# Chroma-Color.net
KiCad netlist of a schematic drawn in EAGLE
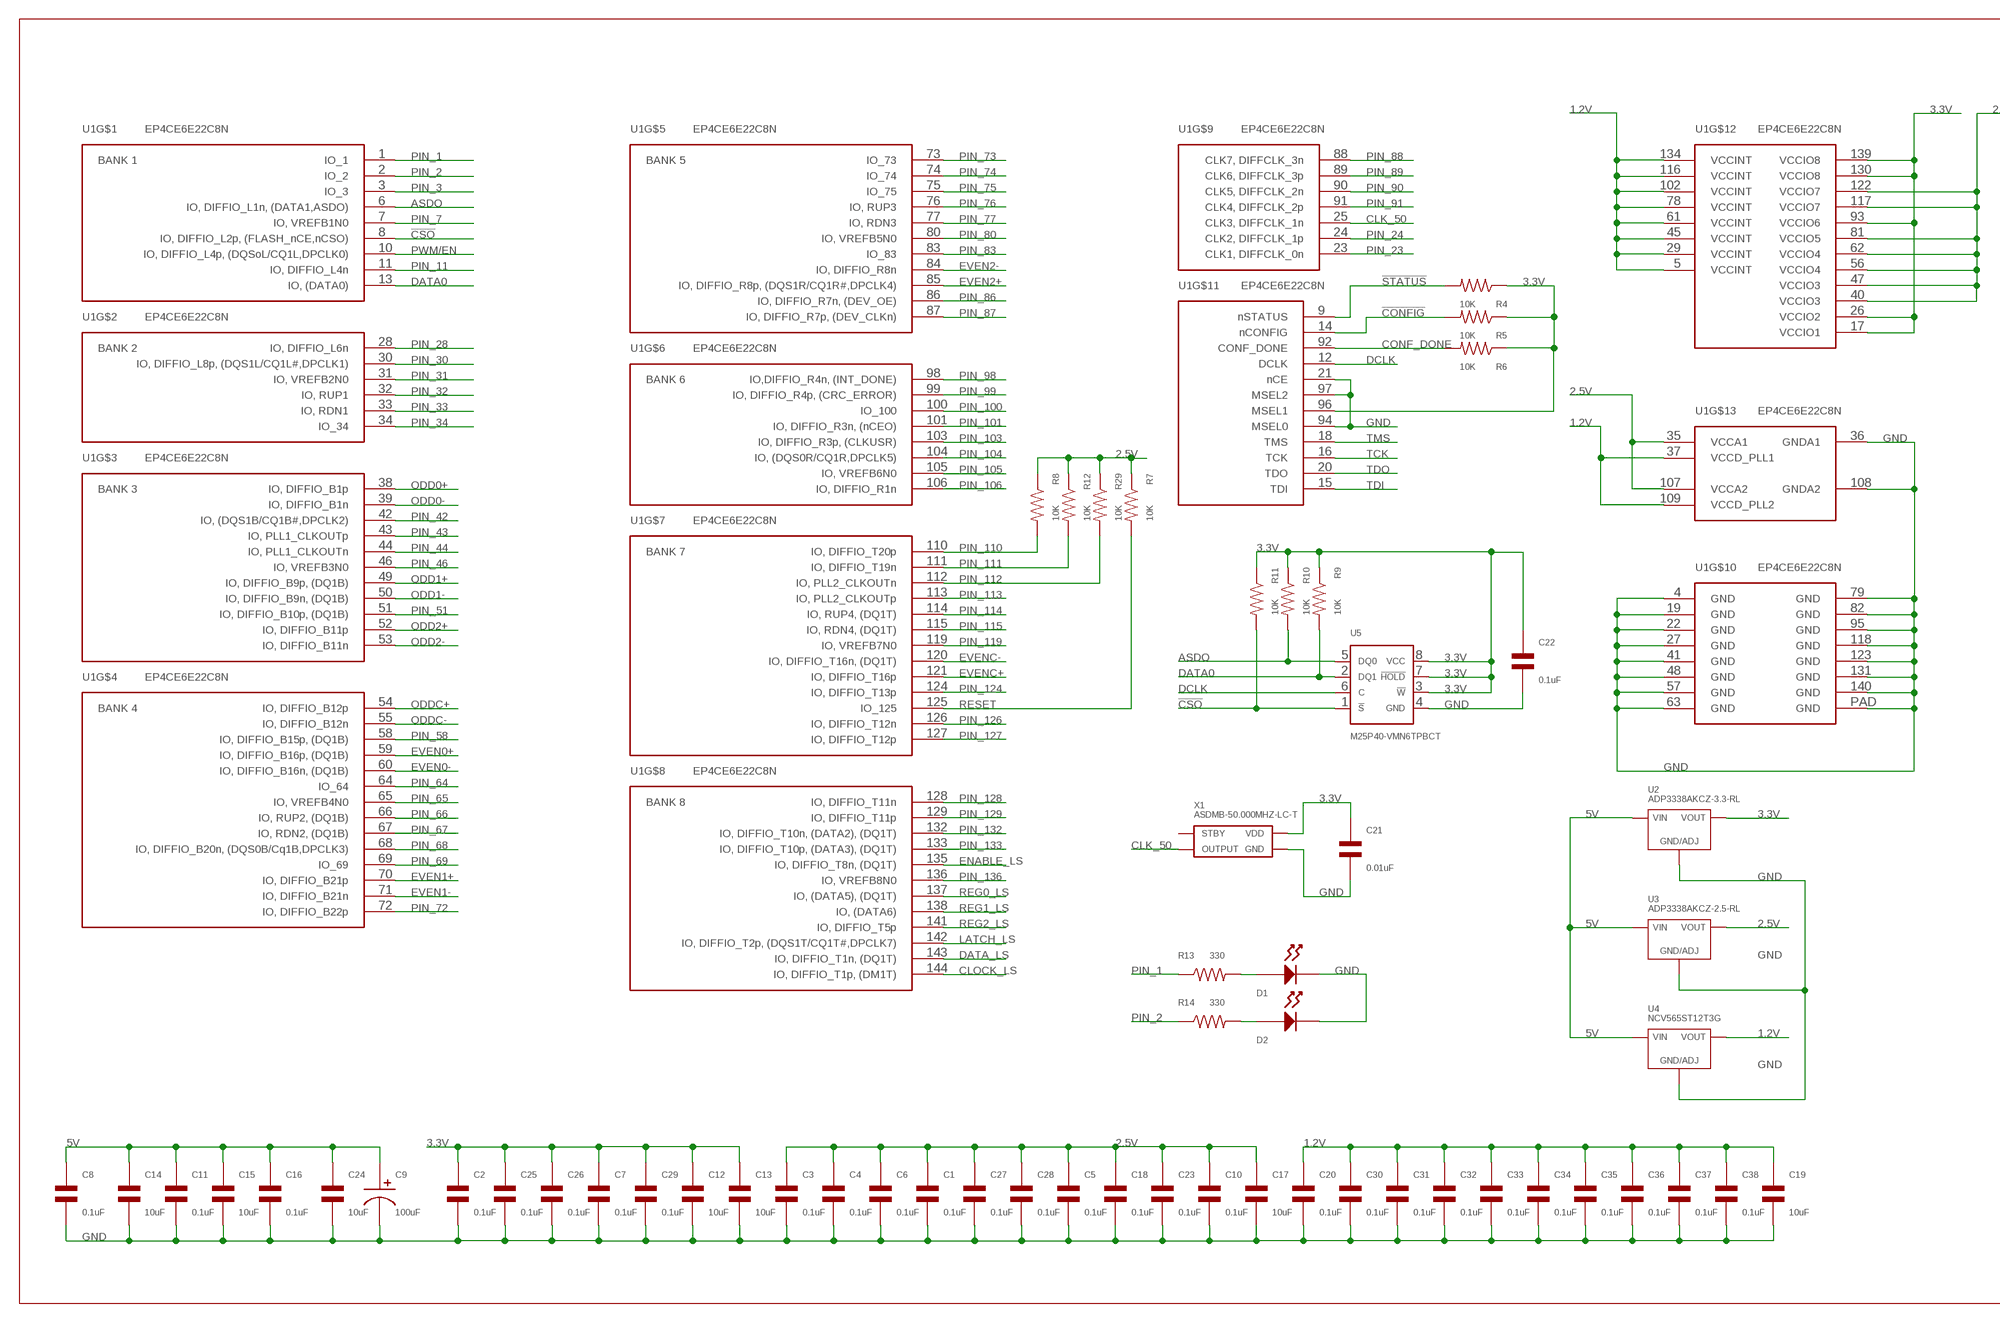
[diagram p0: schematic, sheet 1, part 1 of 2]
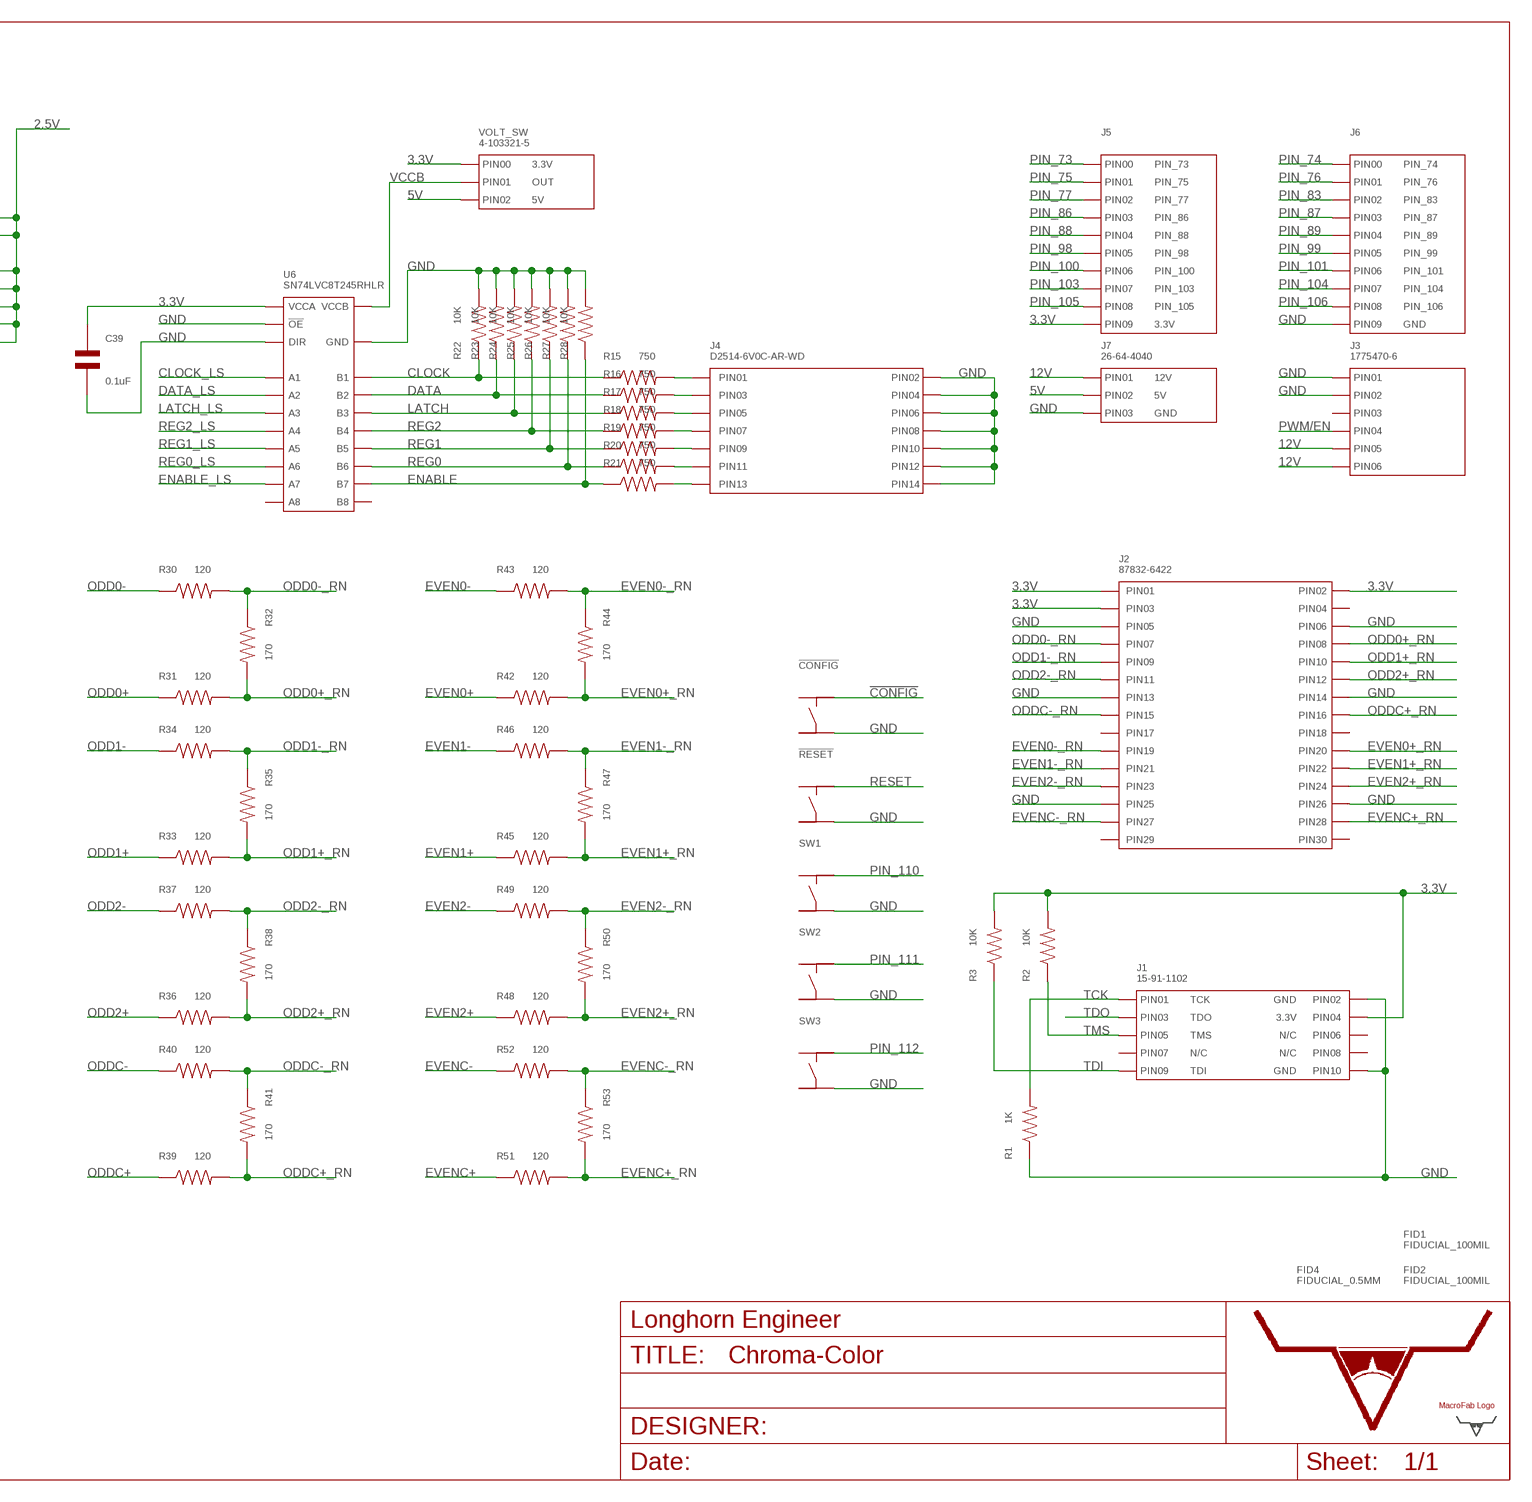
[diagram p1: schematic, sheet 1, part 2 of 2]

(export (version "E")
  (design (tool "Eeschema 10.0.6"))
  (components
    (comp (ref "!CONFIG")
      (value "TACT_4.2MM")
      (footprint "eagle-import:TACT4.2MM")
      (libsource (lib "eagle-import") (part "TACT_4.2MM"))
    )
    (comp (ref "!RESET")
      (value "TACT_4.2MM")
      (footprint "eagle-import:TACT4.2MM")
      (libsource (lib "eagle-import") (part "TACT_4.2MM"))
    )
    (comp (ref "C1")
      (value "0.1uF")
      (footprint "eagle-import:C0603")
      (libsource (lib "eagle-import") (part "CAPACITOR_NP_0603"))
    )
    (comp (ref "C2")
      (value "0.1uF")
      (footprint "eagle-import:C0603")
      (libsource (lib "eagle-import") (part "CAPACITOR_NP_0603"))
    )
    (comp (ref "C3")
      (value "0.1uF")
      (footprint "eagle-import:C0603")
      (libsource (lib "eagle-import") (part "CAPACITOR_NP_0603"))
    )
    (comp (ref "C4")
      (value "0.1uF")
      (footprint "eagle-import:C0603")
      (libsource (lib "eagle-import") (part "CAPACITOR_NP_0603"))
    )
    (comp (ref "C5")
      (value "0.1uF")
      (footprint "eagle-import:C0603")
      (libsource (lib "eagle-import") (part "CAPACITOR_NP_0603"))
    )
    (comp (ref "C6")
      (value "0.1uF")
      (footprint "eagle-import:C0603")
      (libsource (lib "eagle-import") (part "CAPACITOR_NP_0603"))
    )
    (comp (ref "C7")
      (value "0.1uF")
      (footprint "eagle-import:C0603")
      (libsource (lib "eagle-import") (part "CAPACITOR_NP_0603"))
    )
    (comp (ref "C8")
      (value "0.1uF")
      (footprint "eagle-import:C0603")
      (libsource (lib "eagle-import") (part "CAPACITOR_NP_0603"))
    )
    (comp (ref "C9")
      (value "100uF")
      (footprint "eagle-import:CP6.3MM")
      (libsource (lib "eagle-import") (part "CAPACITOR_P_6.3MM"))
    )
    (comp (ref "C10")
      (value "0.1uF")
      (footprint "eagle-import:C0603")
      (libsource (lib "eagle-import") (part "CAPACITOR_NP_0603"))
    )
    (comp (ref "C11")
      (value "0.1uF")
      (footprint "eagle-import:C0603")
      (libsource (lib "eagle-import") (part "CAPACITOR_NP_0603"))
    )
    (comp (ref "C12")
      (value "10uF")
      (footprint "eagle-import:C0603")
      (libsource (lib "eagle-import") (part "CAPACITOR_NP_0603"))
    )
    (comp (ref "C13")
      (value "10uF")
      (footprint "eagle-import:C0603")
      (libsource (lib "eagle-import") (part "CAPACITOR_NP_0603"))
    )
    (comp (ref "C14")
      (value "10uF")
      (footprint "eagle-import:C0603")
      (libsource (lib "eagle-import") (part "CAPACITOR_NP_0603"))
    )
    (comp (ref "C15")
      (value "10uF")
      (footprint "eagle-import:C0603")
      (libsource (lib "eagle-import") (part "CAPACITOR_NP_0603"))
    )
    (comp (ref "C16")
      (value "0.1uF")
      (footprint "eagle-import:C0603")
      (libsource (lib "eagle-import") (part "CAPACITOR_NP_0603"))
    )
    (comp (ref "C17")
      (value "10uF")
      (footprint "eagle-import:C0603")
      (libsource (lib "eagle-import") (part "CAPACITOR_NP_0603"))
    )
    (comp (ref "C18")
      (value "0.1uF")
      (footprint "eagle-import:C0603")
      (libsource (lib "eagle-import") (part "CAPACITOR_NP_0603"))
    )
    (comp (ref "C19")
      (value "10uF")
      (footprint "eagle-import:C0603")
      (libsource (lib "eagle-import") (part "CAPACITOR_NP_0603"))
    )
    (comp (ref "C20")
      (value "0.1uF")
      (footprint "eagle-import:C0603")
      (libsource (lib "eagle-import") (part "CAPACITOR_NP_0603"))
    )
    (comp (ref "C21")
      (value "0.01uF")
      (footprint "eagle-import:C0603")
      (libsource (lib "eagle-import") (part "CAPACITOR_NP_0603"))
    )
    (comp (ref "C22")
      (value "0.1uF")
      (footprint "eagle-import:C0603")
      (libsource (lib "eagle-import") (part "CAPACITOR_NP_0603"))
    )
    (comp (ref "C23")
      (value "0.1uF")
      (footprint "eagle-import:C0603")
      (libsource (lib "eagle-import") (part "CAPACITOR_NP_0603"))
    )
    (comp (ref "C24")
      (value "10uF")
      (footprint "eagle-import:C0603")
      (libsource (lib "eagle-import") (part "CAPACITOR_NP_0603"))
    )
    (comp (ref "C25")
      (value "0.1uF")
      (footprint "eagle-import:C0603")
      (libsource (lib "eagle-import") (part "CAPACITOR_NP_0603"))
    )
    (comp (ref "C26")
      (value "0.1uF")
      (footprint "eagle-import:C0603")
      (libsource (lib "eagle-import") (part "CAPACITOR_NP_0603"))
    )
    (comp (ref "C27")
      (value "0.1uF")
      (footprint "eagle-import:C0603")
      (libsource (lib "eagle-import") (part "CAPACITOR_NP_0603"))
    )
    (comp (ref "C28")
      (value "0.1uF")
      (footprint "eagle-import:C0603")
      (libsource (lib "eagle-import") (part "CAPACITOR_NP_0603"))
    )
    (comp (ref "C29")
      (value "0.1uF")
      (footprint "eagle-import:C0603")
      (libsource (lib "eagle-import") (part "CAPACITOR_NP_0603"))
    )
    (comp (ref "C30")
      (value "0.1uF")
      (footprint "eagle-import:C0603")
      (libsource (lib "eagle-import") (part "CAPACITOR_NP_0603"))
    )
    (comp (ref "C31")
      (value "0.1uF")
      (footprint "eagle-import:C0603")
      (libsource (lib "eagle-import") (part "CAPACITOR_NP_0603"))
    )
    (comp (ref "C32")
      (value "0.1uF")
      (footprint "eagle-import:C0603")
      (libsource (lib "eagle-import") (part "CAPACITOR_NP_0603"))
    )
    (comp (ref "C33")
      (value "0.1uF")
      (footprint "eagle-import:C0603")
      (libsource (lib "eagle-import") (part "CAPACITOR_NP_0603"))
    )
    (comp (ref "C34")
      (value "0.1uF")
      (footprint "eagle-import:C0603")
      (libsource (lib "eagle-import") (part "CAPACITOR_NP_0603"))
    )
    (comp (ref "C35")
      (value "0.1uF")
      (footprint "eagle-import:C0603")
      (libsource (lib "eagle-import") (part "CAPACITOR_NP_0603"))
    )
    (comp (ref "C36")
      (value "0.1uF")
      (footprint "eagle-import:C0603")
      (libsource (lib "eagle-import") (part "CAPACITOR_NP_0603"))
    )
    (comp (ref "C37")
      (value "0.1uF")
      (footprint "eagle-import:C0603")
      (libsource (lib "eagle-import") (part "CAPACITOR_NP_0603"))
    )
    (comp (ref "C38")
      (value "0.1uF")
      (footprint "eagle-import:C0603")
      (libsource (lib "eagle-import") (part "CAPACITOR_NP_0603"))
    )
    (comp (ref "C39")
      (value "0.1uF")
      (footprint "eagle-import:C0603")
      (libsource (lib "eagle-import") (part "CAPACITOR_NP_0603"))
    )
    (comp (ref "D1")
      (value "LED_SINGLE_0805")
      (footprint "eagle-import:LED0805")
      (libsource (lib "eagle-import") (part "LED_SINGLE_0805"))
    )
    (comp (ref "D2")
      (value "LED_SINGLE_0805")
      (footprint "eagle-import:LED0805")
      (libsource (lib "eagle-import") (part "LED_SINGLE_0805"))
    )
    (comp (ref "FID1")
      (value "FIDUCIAL_100MIL")
      (footprint "eagle-import:FIDUCIAL_100MIL")
      (libsource (lib "eagle-import") (part "FIDUCIAL_100MIL"))
    )
    (comp (ref "FID2")
      (value "FIDUCIAL_100MIL")
      (footprint "eagle-import:FIDUCIAL_100MIL")
      (libsource (lib "eagle-import") (part "FIDUCIAL_100MIL"))
    )
    (comp (ref "FID4")
      (value "FIDUCIAL_0.5MM")
      (footprint "eagle-import:FIDUCIAL_0.5MM")
      (libsource (lib "eagle-import") (part "FIDUCIAL_0.5MM"))
    )
    (comp (ref "J1")
      (value "15-91-1102")
      (footprint "eagle-import:15-91-1102")
      (fields
        (field (name "LABEL01") "TCK")
        (field (name "LABEL02") "GND")
        (field (name "LABEL03") "TDO")
        (field (name "LABEL04") "3.3V")
        (field (name "LABEL05") "TMS")
        (field (name "LABEL06") "N/C")
        (field (name "LABEL07") "N/C")
        (field (name "LABEL08") "N/C")
        (field (name "LABEL09") "TDI")
        (field (name "LABEL10") "GND")
      )
      (libsource (lib "eagle-import") (part "CON_02X05_15-91-1102"))
    )
    (comp (ref "J2")
      (value "87832-6422")
      (footprint "eagle-import:87832-6422")
      (libsource (lib "eagle-import") (part "CON_02X15_87832-6422"))
    )
    (comp (ref "J3")
      (value "1775470-6")
      (footprint "eagle-import:1775470-6")
      (libsource (lib "eagle-import") (part "CON_01X06_1775470-6"))
    )
    (comp (ref "J4")
      (value "D2514-6V0C-AR-WD")
      (footprint "eagle-import:D2514-6V0C-AR-WD")
      (libsource (lib "eagle-import") (part "CON_02X07_D2514-6V0C-AR-WD"))
    )
    (comp (ref "J5")
      (value "HEADER_01X10_PTH_2.54MM")
      (footprint "eagle-import:PTH_2.54MM_01X10")
      (fields
        (field (name "LABEL00") "PIN_73")
        (field (name "LABEL01") "PIN_75")
        (field (name "LABEL02") "PIN_77")
        (field (name "LABEL03") "PIN_86")
        (field (name "LABEL04") "PIN_88")
        (field (name "LABEL05") "PIN_98")
        (field (name "LABEL06") "PIN_100")
        (field (name "LABEL07") "PIN_103")
        (field (name "LABEL08") "PIN_105")
        (field (name "LABEL09") "3.3V")
      )
      (libsource (lib "eagle-import") (part "HEADER_01X10_PTH_2.54MM"))
    )
    (comp (ref "J6")
      (value "HEADER_01X10_PTH_2.54MM")
      (footprint "eagle-import:PTH_2.54MM_01X10")
      (fields
        (field (name "LABEL00") "PIN_74")
        (field (name "LABEL01") "PIN_76")
        (field (name "LABEL02") "PIN_83")
        (field (name "LABEL03") "PIN_87")
        (field (name "LABEL04") "PIN_89")
        (field (name "LABEL05") "PIN_99")
        (field (name "LABEL06") "PIN_101")
        (field (name "LABEL07") "PIN_104")
        (field (name "LABEL08") "PIN_106")
        (field (name "LABEL09") "GND")
      )
      (libsource (lib "eagle-import") (part "HEADER_01X10_PTH_2.54MM"))
    )
    (comp (ref "J7")
      (value "26-64-4040")
      (footprint "eagle-import:26-64-4040(KEYPIN1)")
      (fields (field (name "LABEL01") "12V") (field (name "LABEL02") "5V") (field (name "LABEL03") "GND"))
      (libsource (lib "eagle-import") (part "CON_01X03_26-64-4040_(KEYPIN1)"))
    )
    (comp (ref "R1")
      (value "1K")
      (footprint "eagle-import:R0603")
      (libsource (lib "eagle-import") (part "RESISTOR_0603"))
    )
    (comp (ref "R2")
      (value "10K")
      (footprint "eagle-import:R0603")
      (libsource (lib "eagle-import") (part "RESISTOR_0603"))
    )
    (comp (ref "R3")
      (value "10K")
      (footprint "eagle-import:R0603")
      (libsource (lib "eagle-import") (part "RESISTOR_0603"))
    )
    (comp (ref "R4")
      (value "10K")
      (footprint "eagle-import:R0603")
      (libsource (lib "eagle-import") (part "RESISTOR_0603"))
    )
    (comp (ref "R5")
      (value "10K")
      (footprint "eagle-import:R0603")
      (libsource (lib "eagle-import") (part "RESISTOR_0603"))
    )
    (comp (ref "R6")
      (value "10K")
      (footprint "eagle-import:R0603")
      (libsource (lib "eagle-import") (part "RESISTOR_0603"))
    )
    (comp (ref "R7")
      (value "10K")
      (footprint "eagle-import:R0603")
      (libsource (lib "eagle-import") (part "RESISTOR_0603"))
    )
    (comp (ref "R8")
      (value "10K")
      (footprint "eagle-import:R0603")
      (libsource (lib "eagle-import") (part "RESISTOR_0603"))
    )
    (comp (ref "R9")
      (value "10K")
      (footprint "eagle-import:R0603")
      (libsource (lib "eagle-import") (part "RESISTOR_0603"))
    )
    (comp (ref "R10")
      (value "10K")
      (footprint "eagle-import:R0603")
      (libsource (lib "eagle-import") (part "RESISTOR_0603"))
    )
    (comp (ref "R11")
      (value "10K")
      (footprint "eagle-import:R0603")
      (libsource (lib "eagle-import") (part "RESISTOR_0603"))
    )
    (comp (ref "R12")
      (value "10K")
      (footprint "eagle-import:R0603")
      (libsource (lib "eagle-import") (part "RESISTOR_0603"))
    )
    (comp (ref "R13")
      (value "330")
      (footprint "eagle-import:R0603")
      (libsource (lib "eagle-import") (part "RESISTOR_0603"))
    )
    (comp (ref "R14")
      (value "330")
      (footprint "eagle-import:R0603")
      (libsource (lib "eagle-import") (part "RESISTOR_0603"))
    )
    (comp (ref "R15")
      (value "750")
      (footprint "eagle-import:R0603")
      (libsource (lib "eagle-import") (part "RESISTOR_0603"))
    )
    (comp (ref "R16")
      (value "750")
      (footprint "eagle-import:R0603")
      (libsource (lib "eagle-import") (part "RESISTOR_0603"))
    )
    (comp (ref "R17")
      (value "750")
      (footprint "eagle-import:R0603")
      (libsource (lib "eagle-import") (part "RESISTOR_0603"))
    )
    (comp (ref "R18")
      (value "750")
      (footprint "eagle-import:R0603")
      (libsource (lib "eagle-import") (part "RESISTOR_0603"))
    )
    (comp (ref "R19")
      (value "750")
      (footprint "eagle-import:R0603")
      (libsource (lib "eagle-import") (part "RESISTOR_0603"))
    )
    (comp (ref "R20")
      (value "750")
      (footprint "eagle-import:R0603")
      (libsource (lib "eagle-import") (part "RESISTOR_0603"))
    )
    (comp (ref "R21")
      (value "750")
      (footprint "eagle-import:R0603")
      (libsource (lib "eagle-import") (part "RESISTOR_0603"))
    )
    (comp (ref "R22")
      (value "10K")
      (footprint "eagle-import:R0603")
      (libsource (lib "eagle-import") (part "RESISTOR_0603"))
    )
    (comp (ref "R23")
      (value "10K")
      (footprint "eagle-import:R0603")
      (libsource (lib "eagle-import") (part "RESISTOR_0603"))
    )
    (comp (ref "R24")
      (value "10K")
      (footprint "eagle-import:R0603")
      (libsource (lib "eagle-import") (part "RESISTOR_0603"))
    )
    (comp (ref "R25")
      (value "10K")
      (footprint "eagle-import:R0603")
      (libsource (lib "eagle-import") (part "RESISTOR_0603"))
    )
    (comp (ref "R26")
      (value "10K")
      (footprint "eagle-import:R0603")
      (libsource (lib "eagle-import") (part "RESISTOR_0603"))
    )
    (comp (ref "R27")
      (value "10K")
      (footprint "eagle-import:R0603")
      (libsource (lib "eagle-import") (part "RESISTOR_0603"))
    )
    (comp (ref "R28")
      (value "10K")
      (footprint "eagle-import:R0603")
      (libsource (lib "eagle-import") (part "RESISTOR_0603"))
    )
    (comp (ref "R29")
      (value "10K")
      (footprint "eagle-import:R0603")
      (libsource (lib "eagle-import") (part "RESISTOR_0603"))
    )
    (comp (ref "R30")
      (value "120")
      (footprint "eagle-import:R0402")
      (libsource (lib "eagle-import") (part "RESISTOR_0402"))
    )
    (comp (ref "R31")
      (value "120")
      (footprint "eagle-import:R0402")
      (libsource (lib "eagle-import") (part "RESISTOR_0402"))
    )
    (comp (ref "R32")
      (value "170")
      (footprint "eagle-import:R0402")
      (libsource (lib "eagle-import") (part "RESISTOR_0402"))
    )
    (comp (ref "R33")
      (value "120")
      (footprint "eagle-import:R0402")
      (libsource (lib "eagle-import") (part "RESISTOR_0402"))
    )
    (comp (ref "R34")
      (value "120")
      (footprint "eagle-import:R0402")
      (libsource (lib "eagle-import") (part "RESISTOR_0402"))
    )
    (comp (ref "R35")
      (value "170")
      (footprint "eagle-import:R0402")
      (libsource (lib "eagle-import") (part "RESISTOR_0402"))
    )
    (comp (ref "R36")
      (value "120")
      (footprint "eagle-import:R0402")
      (libsource (lib "eagle-import") (part "RESISTOR_0402"))
    )
    (comp (ref "R37")
      (value "120")
      (footprint "eagle-import:R0402")
      (libsource (lib "eagle-import") (part "RESISTOR_0402"))
    )
    (comp (ref "R38")
      (value "170")
      (footprint "eagle-import:R0402")
      (libsource (lib "eagle-import") (part "RESISTOR_0402"))
    )
    (comp (ref "R39")
      (value "120")
      (footprint "eagle-import:R0402")
      (libsource (lib "eagle-import") (part "RESISTOR_0402"))
    )
    (comp (ref "R40")
      (value "120")
      (footprint "eagle-import:R0402")
      (libsource (lib "eagle-import") (part "RESISTOR_0402"))
    )
    (comp (ref "R41")
      (value "170")
      (footprint "eagle-import:R0402")
      (libsource (lib "eagle-import") (part "RESISTOR_0402"))
    )
    (comp (ref "R42")
      (value "120")
      (footprint "eagle-import:R0402")
      (libsource (lib "eagle-import") (part "RESISTOR_0402"))
    )
    (comp (ref "R43")
      (value "120")
      (footprint "eagle-import:R0402")
      (libsource (lib "eagle-import") (part "RESISTOR_0402"))
    )
    (comp (ref "R44")
      (value "170")
      (footprint "eagle-import:R0402")
      (libsource (lib "eagle-import") (part "RESISTOR_0402"))
    )
    (comp (ref "R45")
      (value "120")
      (footprint "eagle-import:R0402")
      (libsource (lib "eagle-import") (part "RESISTOR_0402"))
    )
    (comp (ref "R46")
      (value "120")
      (footprint "eagle-import:R0402")
      (libsource (lib "eagle-import") (part "RESISTOR_0402"))
    )
    (comp (ref "R47")
      (value "170")
      (footprint "eagle-import:R0402")
      (libsource (lib "eagle-import") (part "RESISTOR_0402"))
    )
    (comp (ref "R48")
      (value "120")
      (footprint "eagle-import:R0402")
      (libsource (lib "eagle-import") (part "RESISTOR_0402"))
    )
    (comp (ref "R49")
      (value "120")
      (footprint "eagle-import:R0402")
      (libsource (lib "eagle-import") (part "RESISTOR_0402"))
    )
    (comp (ref "R50")
      (value "170")
      (footprint "eagle-import:R0402")
      (libsource (lib "eagle-import") (part "RESISTOR_0402"))
    )
    (comp (ref "R51")
      (value "120")
      (footprint "eagle-import:R0402")
      (libsource (lib "eagle-import") (part "RESISTOR_0402"))
    )
    (comp (ref "R52")
      (value "120")
      (footprint "eagle-import:R0402")
      (libsource (lib "eagle-import") (part "RESISTOR_0402"))
    )
    (comp (ref "R53")
      (value "170")
      (footprint "eagle-import:R0402")
      (libsource (lib "eagle-import") (part "RESISTOR_0402"))
    )
    (comp (ref "SW1")
      (value "TACT_4.2MM")
      (footprint "eagle-import:TACT4.2MM")
      (libsource (lib "eagle-import") (part "TACT_4.2MM"))
    )
    (comp (ref "SW2")
      (value "TACT_4.2MM")
      (footprint "eagle-import:TACT4.2MM")
      (libsource (lib "eagle-import") (part "TACT_4.2MM"))
    )
    (comp (ref "SW3")
      (value "TACT_4.2MM")
      (footprint "eagle-import:TACT4.2MM")
      (libsource (lib "eagle-import") (part "TACT_4.2MM"))
    )
    (comp (ref "U$1")
      (value "LHE_FRAME")
      (footprint "eagle-import:LHE_FRAME")
      (fields (field (name "DNAME") "Parker Dillmann") (field (name "REVNUM") "REV: 2"))
      (libsource (lib "eagle-import") (part "LHE_FRAME"))
    )
    (comp (ref "U$2")
      (value "MF_LOGOLOGO_MEDIUM")
      (footprint "eagle-import:MF_LOGO_MEDIUM")
      (libsource (lib "eagle-import") (part "MF_LOGOLOGO_MEDIUM"))
    )
    (comp (ref "U$3")
      (value "LHE_LOGOLHE_LOGO")
      (footprint "eagle-import:LHE_LOGO")
      (libsource (lib "eagle-import") (part "LHE_LOGOLHE_LOGO"))
    )
    (comp (ref "U1")
      (value "EP4CE6E22C8N")
      (footprint "eagle-import:EQFP-144")
      (libsource (lib "eagle-import") (part "EP4CE6E22C8N"))
    )
    (comp (ref "U2")
      (value "ADP3338AKCZ-3.3-RL")
      (footprint "eagle-import:ADP3338_SOT-223-3")
      (libsource (lib "eagle-import") (part "LINEAR_VOTLAGE_REGULATORS_ADP3338"))
    )
    (comp (ref "U3")
      (value "ADP3338AKCZ-2.5-RL")
      (footprint "eagle-import:ADP3338_SOT-223-3")
      (libsource (lib "eagle-import") (part "LINEAR_VOTLAGE_REGULATORS_ADP3338"))
    )
    (comp (ref "U4")
      (value "NCV565ST12T3G")
      (footprint "eagle-import:NCV565_SOT-223-3")
      (libsource (lib "eagle-import") (part "LINEAR_VOTLAGE_REGULATORS_NCV565ST12T3G"))
    )
    (comp (ref "U5")
      (value "M25P40-VMN6TPBCT")
      (footprint "eagle-import:M25P40_SOIC-8")
      (libsource (lib "eagle-import") (part "M25P40-VMN6TPBCT"))
    )
    (comp (ref "U6")
      (value "SN74LVC8T245RHLR")
      (footprint "eagle-import:SN74LVC8T245_VQFN-24")
      (libsource (lib "eagle-import") (part "SN74LVC8T245_RHL"))
    )
    (comp (ref "VOLT_SW")
      (value "4-103321-5")
      (footprint "eagle-import:PTH_2.54MM_01X03")
      (fields (field (name "LABEL00") "3.3V") (field (name "LABEL01") "OUT") (field (name "LABEL02") "5V"))
      (libsource (lib "eagle-import") (part "HEADER_01X03_PTH_2.54MM"))
    )
    (comp (ref "X1")
      (value "ASDMB-50.000MHZ-LC-T")
      (footprint "eagle-import:ASDMB")
      (libsource (lib "eagle-import") (part "ASDMB"))
    )
  )
  (nets
    (net (code "1") (name "/1.2V") (class "Default")
      (node (ref "C19") (pin "P$1") (pinfunction "P$1_P$1") (pintype "passive"))
      (node (ref "C20") (pin "P$1") (pinfunction "P$1_P$1") (pintype "passive"))
      (node (ref "C30") (pin "P$1") (pinfunction "P$1_P$1") (pintype "passive"))
      (node (ref "C31") (pin "P$1") (pinfunction "P$1_P$1") (pintype "passive"))
      (node (ref "C32") (pin "P$1") (pinfunction "P$1_P$1") (pintype "passive"))
      (node (ref "C33") (pin "P$1") (pinfunction "P$1_P$1") (pintype "passive"))
      (node (ref "C34") (pin "P$1") (pinfunction "P$1_P$1") (pintype "passive"))
      (node (ref "C35") (pin "P$1") (pinfunction "P$1_P$1") (pintype "passive"))
      (node (ref "C36") (pin "P$1") (pinfunction "P$1_P$1") (pintype "passive"))
      (node (ref "C37") (pin "P$1") (pinfunction "P$1_P$1") (pintype "passive"))
      (node (ref "C38") (pin "P$1") (pinfunction "P$1_P$1") (pintype "passive"))
      (node (ref "U1") (pin "102") (pinfunction "102_102") (pintype "bidirectional"))
      (node (ref "U1") (pin "109") (pinfunction "109_109") (pintype "bidirectional"))
      (node (ref "U1") (pin "116") (pinfunction "116_116") (pintype "bidirectional"))
      (node (ref "U1") (pin "134") (pinfunction "134_134") (pintype "bidirectional"))
      (node (ref "U1") (pin "29") (pinfunction "29_29") (pintype "bidirectional"))
      (node (ref "U1") (pin "37") (pinfunction "37_37") (pintype "bidirectional"))
      (node (ref "U1") (pin "45") (pinfunction "45_45") (pintype "bidirectional"))
      (node (ref "U1") (pin "5") (pinfunction "5_5") (pintype "bidirectional"))
      (node (ref "U1") (pin "61") (pinfunction "61_61") (pintype "bidirectional"))
      (node (ref "U1") (pin "78") (pinfunction "78_78") (pintype "bidirectional"))
      (node (ref "U4") (pin "2") (pinfunction "OUT_2") (pintype "bidirectional"))
      (node (ref "U4") (pin "PAD") (pinfunction "OUT_PAD") (pintype "bidirectional"))
    )
    (net (code "2") (name "/2.5V") (class "Default")
      (node (ref "C1") (pin "P$1") (pinfunction "P$1_P$1") (pintype "passive"))
      (node (ref "C10") (pin "P$1") (pinfunction "P$1_P$1") (pintype "passive"))
      (node (ref "C17") (pin "P$1") (pinfunction "P$1_P$1") (pintype "passive"))
      (node (ref "C18") (pin "P$1") (pinfunction "P$1_P$1") (pintype "passive"))
      (node (ref "C23") (pin "P$1") (pinfunction "P$1_P$1") (pintype "passive"))
      (node (ref "C27") (pin "P$1") (pinfunction "P$1_P$1") (pintype "passive"))
      (node (ref "C28") (pin "P$1") (pinfunction "P$1_P$1") (pintype "passive"))
      (node (ref "C3") (pin "P$1") (pinfunction "P$1_P$1") (pintype "passive"))
      (node (ref "C4") (pin "P$1") (pinfunction "P$1_P$1") (pintype "passive"))
      (node (ref "C5") (pin "P$1") (pinfunction "P$1_P$1") (pintype "passive"))
      (node (ref "C6") (pin "P$1") (pinfunction "P$1_P$1") (pintype "passive"))
      (node (ref "R12") (pin "P$1") (pinfunction "P$1_P$1") (pintype "passive"))
      (node (ref "R29") (pin "P$1") (pinfunction "P$1_P$1") (pintype "passive"))
      (node (ref "R7") (pin "P$1") (pinfunction "P$1_P$1") (pintype "passive"))
      (node (ref "R8") (pin "P$1") (pinfunction "P$1_P$1") (pintype "passive"))
      (node (ref "U1") (pin "107") (pinfunction "107_107") (pintype "bidirectional"))
      (node (ref "U1") (pin "117") (pinfunction "117_117") (pintype "bidirectional"))
      (node (ref "U1") (pin "122") (pinfunction "122_122") (pintype "bidirectional"))
      (node (ref "U1") (pin "35") (pinfunction "35_35") (pintype "bidirectional"))
      (node (ref "U1") (pin "40") (pinfunction "40_40") (pintype "bidirectional"))
      (node (ref "U1") (pin "47") (pinfunction "47_47") (pintype "bidirectional"))
      (node (ref "U1") (pin "56") (pinfunction "56_56") (pintype "bidirectional"))
      (node (ref "U1") (pin "62") (pinfunction "62_62") (pintype "bidirectional"))
      (node (ref "U1") (pin "81") (pinfunction "81_81") (pintype "bidirectional"))
      (node (ref "U3") (pin "2") (pinfunction "OUT_2") (pintype "bidirectional"))
      (node (ref "U3") (pin "PAD") (pinfunction "OUT_PAD") (pintype "bidirectional"))
    )
    (net (code "3") (name "/3.3V") (class "Default")
      (node (ref "C12") (pin "P$1") (pinfunction "P$1_P$1") (pintype "passive"))
      (node (ref "C13") (pin "P$1") (pinfunction "P$1_P$1") (pintype "passive"))
      (node (ref "C2") (pin "P$1") (pinfunction "P$1_P$1") (pintype "passive"))
      (node (ref "C21") (pin "P$1") (pinfunction "P$1_P$1") (pintype "passive"))
      (node (ref "C22") (pin "P$1") (pinfunction "P$1_P$1") (pintype "passive"))
      (node (ref "C25") (pin "P$1") (pinfunction "P$1_P$1") (pintype "passive"))
      (node (ref "C26") (pin "P$1") (pinfunction "P$1_P$1") (pintype "passive"))
      (node (ref "C29") (pin "P$1") (pinfunction "P$1_P$1") (pintype "passive"))
      (node (ref "C39") (pin "P$1") (pinfunction "P$1_P$1") (pintype "passive"))
      (node (ref "C7") (pin "P$1") (pinfunction "P$1_P$1") (pintype "passive"))
      (node (ref "J1") (pin "4") (pinfunction "PIN4_4") (pintype "bidirectional"))
      (node (ref "J2") (pin "P$1") (pinfunction "PIN0_P$1") (pintype "bidirectional"))
      (node (ref "J2") (pin "P$2") (pinfunction "PIN1_P$2") (pintype "bidirectional"))
      (node (ref "J2") (pin "P$3") (pinfunction "PIN2_P$3") (pintype "bidirectional"))
      (node (ref "J5") (pin "P$10") (pinfunction "PIN9_P$10") (pintype "bidirectional"))
      (node (ref "R10") (pin "P$1") (pinfunction "P$1_P$1") (pintype "passive"))
      (node (ref "R11") (pin "P$1") (pinfunction "P$1_P$1") (pintype "passive"))
      (node (ref "R2") (pin "P$2") (pinfunction "P$2_P$2") (pintype "passive"))
      (node (ref "R3") (pin "P$2") (pinfunction "P$2_P$2") (pintype "passive"))
      (node (ref "R4") (pin "P$1") (pinfunction "P$1_P$1") (pintype "passive"))
      (node (ref "R5") (pin "P$1") (pinfunction "P$1_P$1") (pintype "passive"))
      (node (ref "R6") (pin "P$1") (pinfunction "P$1_P$1") (pintype "passive"))
      (node (ref "R9") (pin "P$1") (pinfunction "P$1_P$1") (pintype "passive"))
      (node (ref "U1") (pin "130") (pinfunction "130_130") (pintype "bidirectional"))
      (node (ref "U1") (pin "139") (pinfunction "139_139") (pintype "bidirectional"))
      (node (ref "U1") (pin "17") (pinfunction "17_17") (pintype "bidirectional"))
      (node (ref "U1") (pin "26") (pinfunction "26_26") (pintype "bidirectional"))
      (node (ref "U1") (pin "93") (pinfunction "93_93") (pintype "bidirectional"))
      (node (ref "U1") (pin "96") (pinfunction "96_96") (pintype "bidirectional"))
      (node (ref "U2") (pin "2") (pinfunction "OUT_2") (pintype "bidirectional"))
      (node (ref "U2") (pin "PAD") (pinfunction "OUT_PAD") (pintype "bidirectional"))
      (node (ref "U5") (pin "3") (pinfunction "~{W}_3") (pintype "bidirectional"))
      (node (ref "U5") (pin "7") (pinfunction "~{HOLD}_7") (pintype "bidirectional"))
      (node (ref "U5") (pin "8") (pinfunction "VCC_8") (pintype "bidirectional"))
      (node (ref "U6") (pin "1") (pinfunction "VCCA_1") (pintype "bidirectional"))
      (node (ref "VOLT_SW") (pin "P$1") (pinfunction "PIN0_P$1") (pintype "bidirectional"))
      (node (ref "X1") (pin "P$4") (pinfunction "VDD_P$4") (pintype "bidirectional"))
    )
    (net (code "4") (name "/5V") (class "Default")
      (node (ref "C11") (pin "P$1") (pinfunction "P$1_P$1") (pintype "passive"))
      (node (ref "C14") (pin "P$1") (pinfunction "P$1_P$1") (pintype "passive"))
      (node (ref "C15") (pin "P$1") (pinfunction "P$1_P$1") (pintype "passive"))
      (node (ref "C16") (pin "P$1") (pinfunction "P$1_P$1") (pintype "passive"))
      (node (ref "C24") (pin "P$1") (pinfunction "P$1_P$1") (pintype "passive"))
      (node (ref "C8") (pin "P$1") (pinfunction "P$1_P$1") (pintype "passive"))
      (node (ref "C9") (pin "P$1") (pinfunction "P$1_P$1") (pintype "passive"))
      (node (ref "J7") (pin "3") (pinfunction "PIN2_3") (pintype "bidirectional"))
      (node (ref "U2") (pin "3") (pinfunction "IN_3") (pintype "bidirectional"))
      (node (ref "U3") (pin "3") (pinfunction "IN_3") (pintype "bidirectional"))
      (node (ref "U4") (pin "3") (pinfunction "IN_3") (pintype "bidirectional"))
      (node (ref "VOLT_SW") (pin "P$3") (pinfunction "PIN2_P$3") (pintype "bidirectional"))
    )
    (net (code "5") (name "/12V") (class "Default")
      (node (ref "J3") (pin "P$5") (pinfunction "5_P$5") (pintype "passive"))
      (node (ref "J3") (pin "P$6") (pinfunction "6_P$6") (pintype "passive"))
      (node (ref "J7") (pin "2") (pinfunction "PIN1_2") (pintype "bidirectional"))
    )
    (net (code "6") (name "/ASDO") (class "Default")
      (node (ref "R10") (pin "P$2") (pinfunction "P$2_P$2") (pintype "passive"))
      (node (ref "U1") (pin "6") (pinfunction "6_6") (pintype "bidirectional"))
      (node (ref "U5") (pin "5") (pinfunction "DQ0_5") (pintype "bidirectional"))
    )
    (net (code "7") (name "/CLK_50") (class "Default")
      (node (ref "U1") (pin "25") (pinfunction "25_25") (pintype "bidirectional"))
      (node (ref "X1") (pin "P$3") (pinfunction "OUTPUT_P$3") (pintype "bidirectional"))
    )
    (net (code "8") (name "/CLOCK") (class "Default")
      (node (ref "R15") (pin "P$1") (pinfunction "P$1_P$1") (pintype "passive"))
      (node (ref "R22") (pin "P$1") (pinfunction "P$1_P$1") (pintype "passive"))
      (node (ref "U6") (pin "21") (pinfunction "B1_21") (pintype "bidirectional"))
    )
    (net (code "9") (name "/CLOCK_LS") (class "Default")
      (node (ref "U1") (pin "144") (pinfunction "144_144") (pintype "bidirectional"))
      (node (ref "U6") (pin "3") (pinfunction "A1_3") (pintype "bidirectional"))
    )
    (net (code "10") (name "/CONF_DONE") (class "Default")
      (node (ref "R6") (pin "P$2") (pinfunction "P$2_P$2") (pintype "passive"))
      (node (ref "U1") (pin "92") (pinfunction "92_92") (pintype "bidirectional"))
    )
    (net (code "11") (name "/DATA") (class "Default")
      (node (ref "R16") (pin "P$1") (pinfunction "P$1_P$1") (pintype "passive"))
      (node (ref "R23") (pin "P$1") (pinfunction "P$1_P$1") (pintype "passive"))
      (node (ref "U6") (pin "20") (pinfunction "B2_20") (pintype "bidirectional"))
    )
    (net (code "12") (name "/DATA0") (class "Default")
      (node (ref "R9") (pin "P$2") (pinfunction "P$2_P$2") (pintype "passive"))
      (node (ref "U1") (pin "13") (pinfunction "13_13") (pintype "bidirectional"))
      (node (ref "U5") (pin "2") (pinfunction "DQ1_2") (pintype "bidirectional"))
    )
    (net (code "13") (name "/DATA_LS") (class "Default")
      (node (ref "U1") (pin "143") (pinfunction "143_143") (pintype "bidirectional"))
      (node (ref "U6") (pin "4") (pinfunction "A2_4") (pintype "bidirectional"))
    )
    (net (code "14") (name "/DCLK") (class "Default")
      (node (ref "U1") (pin "12") (pinfunction "12_12") (pintype "bidirectional"))
      (node (ref "U5") (pin "6") (pinfunction "C_6") (pintype "bidirectional"))
    )
    (net (code "15") (name "/ENABLE") (class "Default")
      (node (ref "R21") (pin "P$1") (pinfunction "P$1_P$1") (pintype "passive"))
      (node (ref "R28") (pin "P$1") (pinfunction "P$1_P$1") (pintype "passive"))
      (node (ref "U6") (pin "15") (pinfunction "B7_15") (pintype "bidirectional"))
    )
    (net (code "16") (name "/ENABLE_LS") (class "Default")
      (node (ref "U1") (pin "135") (pinfunction "135_135") (pintype "bidirectional"))
      (node (ref "U6") (pin "9") (pinfunction "A7_9") (pintype "bidirectional"))
    )
    (net (code "17") (name "/EVEN0+") (class "Default")
      (node (ref "R42") (pin "P$1") (pinfunction "P$1_P$1") (pintype "passive"))
      (node (ref "U1") (pin "59") (pinfunction "59_59") (pintype "bidirectional"))
    )
    (net (code "18") (name "/EVEN0+_RN") (class "Default")
      (node (ref "J2") (pin "P$20") (pinfunction "PIN19_P$20") (pintype "bidirectional"))
      (node (ref "R42") (pin "P$2") (pinfunction "P$2_P$2") (pintype "passive"))
      (node (ref "R44") (pin "P$2") (pinfunction "P$2_P$2") (pintype "passive"))
    )
    (net (code "19") (name "/EVEN0-") (class "Default")
      (node (ref "R43") (pin "P$1") (pinfunction "P$1_P$1") (pintype "passive"))
      (node (ref "U1") (pin "60") (pinfunction "60_60") (pintype "bidirectional"))
    )
    (net (code "20") (name "/EVEN0-_RN") (class "Default")
      (node (ref "J2") (pin "P$19") (pinfunction "PIN18_P$19") (pintype "bidirectional"))
      (node (ref "R43") (pin "P$2") (pinfunction "P$2_P$2") (pintype "passive"))
      (node (ref "R44") (pin "P$1") (pinfunction "P$1_P$1") (pintype "passive"))
    )
    (net (code "21") (name "/EVEN1+") (class "Default")
      (node (ref "R45") (pin "P$1") (pinfunction "P$1_P$1") (pintype "passive"))
      (node (ref "U1") (pin "70") (pinfunction "70_70") (pintype "bidirectional"))
    )
    (net (code "22") (name "/EVEN1+_RN") (class "Default")
      (node (ref "J2") (pin "P$22") (pinfunction "PIN21_P$22") (pintype "bidirectional"))
      (node (ref "R45") (pin "P$2") (pinfunction "P$2_P$2") (pintype "passive"))
      (node (ref "R47") (pin "P$2") (pinfunction "P$2_P$2") (pintype "passive"))
    )
    (net (code "23") (name "/EVEN1-") (class "Default")
      (node (ref "R46") (pin "P$1") (pinfunction "P$1_P$1") (pintype "passive"))
      (node (ref "U1") (pin "71") (pinfunction "71_71") (pintype "bidirectional"))
    )
    (net (code "24") (name "/EVEN1-_RN") (class "Default")
      (node (ref "J2") (pin "P$21") (pinfunction "PIN20_P$21") (pintype "bidirectional"))
      (node (ref "R46") (pin "P$2") (pinfunction "P$2_P$2") (pintype "passive"))
      (node (ref "R47") (pin "P$1") (pinfunction "P$1_P$1") (pintype "passive"))
    )
    (net (code "25") (name "/EVEN2+") (class "Default")
      (node (ref "R48") (pin "P$1") (pinfunction "P$1_P$1") (pintype "passive"))
      (node (ref "U1") (pin "85") (pinfunction "85_85") (pintype "bidirectional"))
    )
    (net (code "26") (name "/EVEN2+_RN") (class "Default")
      (node (ref "J2") (pin "P$24") (pinfunction "PIN23_P$24") (pintype "bidirectional"))
      (node (ref "R48") (pin "P$2") (pinfunction "P$2_P$2") (pintype "passive"))
      (node (ref "R50") (pin "P$2") (pinfunction "P$2_P$2") (pintype "passive"))
    )
    (net (code "27") (name "/EVEN2-") (class "Default")
      (node (ref "R49") (pin "P$1") (pinfunction "P$1_P$1") (pintype "passive"))
      (node (ref "U1") (pin "84") (pinfunction "84_84") (pintype "bidirectional"))
    )
    (net (code "28") (name "/EVEN2-_RN") (class "Default")
      (node (ref "J2") (pin "P$23") (pinfunction "PIN22_P$23") (pintype "bidirectional"))
      (node (ref "R49") (pin "P$2") (pinfunction "P$2_P$2") (pintype "passive"))
      (node (ref "R50") (pin "P$1") (pinfunction "P$1_P$1") (pintype "passive"))
    )
    (net (code "29") (name "/EVENC+") (class "Default")
      (node (ref "R51") (pin "P$1") (pinfunction "P$1_P$1") (pintype "passive"))
      (node (ref "U1") (pin "121") (pinfunction "121_121") (pintype "bidirectional"))
    )
    (net (code "30") (name "/EVENC+_RN") (class "Default")
      (node (ref "J2") (pin "P$28") (pinfunction "PIN27_P$28") (pintype "bidirectional"))
      (node (ref "R51") (pin "P$2") (pinfunction "P$2_P$2") (pintype "passive"))
      (node (ref "R53") (pin "P$2") (pinfunction "P$2_P$2") (pintype "passive"))
    )
    (net (code "31") (name "/EVENC-") (class "Default")
      (node (ref "R52") (pin "P$1") (pinfunction "P$1_P$1") (pintype "passive"))
      (node (ref "U1") (pin "120") (pinfunction "120_120") (pintype "bidirectional"))
    )
    (net (code "32") (name "/EVENC-_RN") (class "Default")
      (node (ref "J2") (pin "P$27") (pinfunction "PIN26_P$27") (pintype "bidirectional"))
      (node (ref "R52") (pin "P$2") (pinfunction "P$2_P$2") (pintype "passive"))
      (node (ref "R53") (pin "P$1") (pinfunction "P$1_P$1") (pintype "passive"))
    )
    (net (code "33") (name "/GND") (class "Default")
      (node (ref "!CONFIG") (pin "P$4") (pinfunction "P$4_P$4") (pintype "bidirectional"))
      (node (ref "!RESET") (pin "P$4") (pinfunction "P$4_P$4") (pintype "bidirectional"))
      (node (ref "C1") (pin "P$2") (pinfunction "P$2_P$2") (pintype "passive"))
      (node (ref "C10") (pin "P$2") (pinfunction "P$2_P$2") (pintype "passive"))
      (node (ref "C11") (pin "P$2") (pinfunction "P$2_P$2") (pintype "passive"))
      (node (ref "C12") (pin "P$2") (pinfunction "P$2_P$2") (pintype "passive"))
      (node (ref "C13") (pin "P$2") (pinfunction "P$2_P$2") (pintype "passive"))
      (node (ref "C14") (pin "P$2") (pinfunction "P$2_P$2") (pintype "passive"))
      (node (ref "C15") (pin "P$2") (pinfunction "P$2_P$2") (pintype "passive"))
      (node (ref "C16") (pin "P$2") (pinfunction "P$2_P$2") (pintype "passive"))
      (node (ref "C17") (pin "P$2") (pinfunction "P$2_P$2") (pintype "passive"))
      (node (ref "C18") (pin "P$2") (pinfunction "P$2_P$2") (pintype "passive"))
      (node (ref "C19") (pin "P$2") (pinfunction "P$2_P$2") (pintype "passive"))
      (node (ref "C2") (pin "P$2") (pinfunction "P$2_P$2") (pintype "passive"))
      (node (ref "C20") (pin "P$2") (pinfunction "P$2_P$2") (pintype "passive"))
      (node (ref "C21") (pin "P$2") (pinfunction "P$2_P$2") (pintype "passive"))
      (node (ref "C22") (pin "P$2") (pinfunction "P$2_P$2") (pintype "passive"))
      (node (ref "C23") (pin "P$2") (pinfunction "P$2_P$2") (pintype "passive"))
      (node (ref "C24") (pin "P$2") (pinfunction "P$2_P$2") (pintype "passive"))
      (node (ref "C25") (pin "P$2") (pinfunction "P$2_P$2") (pintype "passive"))
      (node (ref "C26") (pin "P$2") (pinfunction "P$2_P$2") (pintype "passive"))
      (node (ref "C27") (pin "P$2") (pinfunction "P$2_P$2") (pintype "passive"))
      (node (ref "C28") (pin "P$2") (pinfunction "P$2_P$2") (pintype "passive"))
      (node (ref "C29") (pin "P$2") (pinfunction "P$2_P$2") (pintype "passive"))
      (node (ref "C3") (pin "P$2") (pinfunction "P$2_P$2") (pintype "passive"))
      (node (ref "C30") (pin "P$2") (pinfunction "P$2_P$2") (pintype "passive"))
      (node (ref "C31") (pin "P$2") (pinfunction "P$2_P$2") (pintype "passive"))
      (node (ref "C32") (pin "P$2") (pinfunction "P$2_P$2") (pintype "passive"))
      (node (ref "C33") (pin "P$2") (pinfunction "P$2_P$2") (pintype "passive"))
      (node (ref "C34") (pin "P$2") (pinfunction "P$2_P$2") (pintype "passive"))
      (node (ref "C35") (pin "P$2") (pinfunction "P$2_P$2") (pintype "passive"))
      (node (ref "C36") (pin "P$2") (pinfunction "P$2_P$2") (pintype "passive"))
      (node (ref "C37") (pin "P$2") (pinfunction "P$2_P$2") (pintype "passive"))
      (node (ref "C38") (pin "P$2") (pinfunction "P$2_P$2") (pintype "passive"))
      (node (ref "C39") (pin "P$2") (pinfunction "P$2_P$2") (pintype "passive"))
      (node (ref "C4") (pin "P$2") (pinfunction "P$2_P$2") (pintype "passive"))
      (node (ref "C5") (pin "P$2") (pinfunction "P$2_P$2") (pintype "passive"))
      (node (ref "C6") (pin "P$2") (pinfunction "P$2_P$2") (pintype "passive"))
      (node (ref "C7") (pin "P$2") (pinfunction "P$2_P$2") (pintype "passive"))
      (node (ref "C8") (pin "P$2") (pinfunction "P$2_P$2") (pintype "passive"))
      (node (ref "C9") (pin "P$2") (pinfunction "P$2_P$2") (pintype "passive"))
      (node (ref "D1") (pin "CATHODE") (pinfunction "CATHODE_CATHODE") (pintype "power_in"))
      (node (ref "D2") (pin "CATHODE") (pinfunction "CATHODE_CATHODE") (pintype "power_in"))
      (node (ref "J1") (pin "10") (pinfunction "PIN10_10") (pintype "bidirectional"))
      (node (ref "J1") (pin "2") (pinfunction "PIN2_2") (pintype "bidirectional"))
      (node (ref "J2") (pin "P$13") (pinfunction "PIN12_P$13") (pintype "bidirectional"))
      (node (ref "J2") (pin "P$14") (pinfunction "PIN13_P$14") (pintype "bidirectional"))
      (node (ref "J2") (pin "P$25") (pinfunction "PIN24_P$25") (pintype "bidirectional"))
      (node (ref "J2") (pin "P$26") (pinfunction "PIN25_P$26") (pintype "bidirectional"))
      (node (ref "J2") (pin "P$5") (pinfunction "PIN4_P$5") (pintype "bidirectional"))
      (node (ref "J2") (pin "P$6") (pinfunction "PIN5_P$6") (pintype "bidirectional"))
      (node (ref "J3") (pin "P$1") (pinfunction "1_P$1") (pintype "passive"))
      (node (ref "J3") (pin "P$2") (pinfunction "2_P$2") (pintype "passive"))
      (node (ref "J4") (pin "10") (pinfunction "PIN10_10") (pintype "bidirectional"))
      (node (ref "J4") (pin "12") (pinfunction "PIN12_12") (pintype "bidirectional"))
      (node (ref "J4") (pin "14") (pinfunction "PIN14_14") (pintype "bidirectional"))
      (node (ref "J4") (pin "2") (pinfunction "PIN2_2") (pintype "bidirectional"))
      (node (ref "J4") (pin "4") (pinfunction "PIN4_4") (pintype "bidirectional"))
      (node (ref "J4") (pin "6") (pinfunction "PIN6_6") (pintype "bidirectional"))
      (node (ref "J4") (pin "8") (pinfunction "PIN8_8") (pintype "bidirectional"))
      (node (ref "J6") (pin "P$10") (pinfunction "PIN9_P$10") (pintype "bidirectional"))
      (node (ref "J7") (pin "4") (pinfunction "PIN3_4") (pintype "bidirectional"))
      (node (ref "R1") (pin "P$1") (pinfunction "P$1_P$1") (pintype "passive"))
      (node (ref "R22") (pin "P$2") (pinfunction "P$2_P$2") (pintype "passive"))
      (node (ref "R23") (pin "P$2") (pinfunction "P$2_P$2") (pintype "passive"))
      (node (ref "R24") (pin "P$2") (pinfunction "P$2_P$2") (pintype "passive"))
      (node (ref "R25") (pin "P$2") (pinfunction "P$2_P$2") (pintype "passive"))
      (node (ref "R26") (pin "P$2") (pinfunction "P$2_P$2") (pintype "passive"))
      (node (ref "R27") (pin "P$2") (pinfunction "P$2_P$2") (pintype "passive"))
      (node (ref "R28") (pin "P$2") (pinfunction "P$2_P$2") (pintype "passive"))
      (node (ref "SW1") (pin "P$4") (pinfunction "P$4_P$4") (pintype "bidirectional"))
      (node (ref "SW2") (pin "P$4") (pinfunction "P$4_P$4") (pintype "bidirectional"))
      (node (ref "SW3") (pin "P$4") (pinfunction "P$4_P$4") (pintype "bidirectional"))
      (node (ref "U1") (pin "108") (pinfunction "108_108") (pintype "bidirectional"))
      (node (ref "U1") (pin "118") (pinfunction "118_118") (pintype "bidirectional"))
      (node (ref "U1") (pin "123") (pinfunction "123_123") (pintype "bidirectional"))
      (node (ref "U1") (pin "131") (pinfunction "131_131") (pintype "bidirectional"))
      (node (ref "U1") (pin "140") (pinfunction "140_140") (pintype "bidirectional"))
      (node (ref "U1") (pin "19") (pinfunction "19_19") (pintype "bidirectional"))
      (node (ref "U1") (pin "21") (pinfunction "21_21") (pintype "bidirectional"))
      (node (ref "U1") (pin "22") (pinfunction "22_22") (pintype "bidirectional"))
      (node (ref "U1") (pin "27") (pinfunction "27_27") (pintype "bidirectional"))
      (node (ref "U1") (pin "36") (pinfunction "36_36") (pintype "bidirectional"))
      (node (ref "U1") (pin "4") (pinfunction "4_4") (pintype "bidirectional"))
      (node (ref "U1") (pin "41") (pinfunction "41_41") (pintype "bidirectional"))
      (node (ref "U1") (pin "48") (pinfunction "48_48") (pintype "bidirectional"))
      (node (ref "U1") (pin "57") (pinfunction "57_57") (pintype "bidirectional"))
      (node (ref "U1") (pin "63") (pinfunction "63_63") (pintype "bidirectional"))
      (node (ref "U1") (pin "79") (pinfunction "79_79") (pintype "bidirectional"))
      (node (ref "U1") (pin "82") (pinfunction "82_82") (pintype "bidirectional"))
      (node (ref "U1") (pin "94") (pinfunction "94_94") (pintype "bidirectional"))
      (node (ref "U1") (pin "95") (pinfunction "95_95") (pintype "bidirectional"))
      (node (ref "U1") (pin "97") (pinfunction "97_97") (pintype "bidirectional"))
      (node (ref "U1") (pin "PAD") (pinfunction "145_PAD") (pintype "bidirectional"))
      (node (ref "U2") (pin "1") (pinfunction "GND_1") (pintype "bidirectional"))
      (node (ref "U3") (pin "1") (pinfunction "GND_1") (pintype "bidirectional"))
      (node (ref "U4") (pin "1") (pinfunction "GND_1") (pintype "bidirectional"))
      (node (ref "U5") (pin "4") (pinfunction "GND_4") (pintype "bidirectional"))
      (node (ref "U6") (pin "11") (pinfunction "GND_11") (pintype "bidirectional"))
      (node (ref "U6") (pin "12") (pinfunction "GND_12") (pintype "bidirectional"))
      (node (ref "U6") (pin "13") (pinfunction "GND_13") (pintype "bidirectional"))
      (node (ref "U6") (pin "2") (pinfunction "DIR_2") (pintype "bidirectional"))
      (node (ref "U6") (pin "22") (pinfunction "~{OE}_22") (pintype "bidirectional"))
      (node (ref "X1") (pin "P$2") (pinfunction "GND_P$2") (pintype "bidirectional"))
    )
    (net (code "34") (name "/LATCH") (class "Default")
      (node (ref "R17") (pin "P$1") (pinfunction "P$1_P$1") (pintype "passive"))
      (node (ref "R24") (pin "P$1") (pinfunction "P$1_P$1") (pintype "passive"))
      (node (ref "U6") (pin "19") (pinfunction "B3_19") (pintype "bidirectional"))
    )
    (net (code "35") (name "/LATCH_LS") (class "Default")
      (node (ref "U1") (pin "142") (pinfunction "142_142") (pintype "bidirectional"))
      (node (ref "U6") (pin "5") (pinfunction "A3_5") (pintype "bidirectional"))
    )
    (net (code "36") (name "/ODD0+") (class "Default")
      (node (ref "R31") (pin "P$1") (pinfunction "P$1_P$1") (pintype "passive"))
      (node (ref "U1") (pin "38") (pinfunction "38_38") (pintype "bidirectional"))
    )
    (net (code "37") (name "/ODD0+_RN") (class "Default")
      (node (ref "J2") (pin "P$8") (pinfunction "PIN7_P$8") (pintype "bidirectional"))
      (node (ref "R31") (pin "P$2") (pinfunction "P$2_P$2") (pintype "passive"))
      (node (ref "R32") (pin "P$2") (pinfunction "P$2_P$2") (pintype "passive"))
    )
    (net (code "38") (name "/ODD0-") (class "Default")
      (node (ref "R30") (pin "P$1") (pinfunction "P$1_P$1") (pintype "passive"))
      (node (ref "U1") (pin "39") (pinfunction "39_39") (pintype "bidirectional"))
    )
    (net (code "39") (name "/ODD0-_RN") (class "Default")
      (node (ref "J2") (pin "P$7") (pinfunction "PIN6_P$7") (pintype "bidirectional"))
      (node (ref "R30") (pin "P$2") (pinfunction "P$2_P$2") (pintype "passive"))
      (node (ref "R32") (pin "P$1") (pinfunction "P$1_P$1") (pintype "passive"))
    )
    (net (code "40") (name "/ODD1+") (class "Default")
      (node (ref "R33") (pin "P$1") (pinfunction "P$1_P$1") (pintype "passive"))
      (node (ref "U1") (pin "49") (pinfunction "49_49") (pintype "bidirectional"))
    )
    (net (code "41") (name "/ODD1+_RN") (class "Default")
      (node (ref "J2") (pin "P$10") (pinfunction "PIN9_P$10") (pintype "bidirectional"))
      (node (ref "R33") (pin "P$2") (pinfunction "P$2_P$2") (pintype "passive"))
      (node (ref "R35") (pin "P$2") (pinfunction "P$2_P$2") (pintype "passive"))
    )
    (net (code "42") (name "/ODD1-") (class "Default")
      (node (ref "R34") (pin "P$1") (pinfunction "P$1_P$1") (pintype "passive"))
      (node (ref "U1") (pin "50") (pinfunction "50_50") (pintype "bidirectional"))
    )
    (net (code "43") (name "/ODD1-_RN") (class "Default")
      (node (ref "J2") (pin "P$9") (pinfunction "PIN8_P$9") (pintype "bidirectional"))
      (node (ref "R34") (pin "P$2") (pinfunction "P$2_P$2") (pintype "passive"))
      (node (ref "R35") (pin "P$1") (pinfunction "P$1_P$1") (pintype "passive"))
    )
    (net (code "44") (name "/ODD2+") (class "Default")
      (node (ref "R36") (pin "P$1") (pinfunction "P$1_P$1") (pintype "passive"))
      (node (ref "U1") (pin "52") (pinfunction "52_52") (pintype "bidirectional"))
    )
    (net (code "45") (name "/ODD2+_RN") (class "Default")
      (node (ref "J2") (pin "P$12") (pinfunction "PIN11_P$12") (pintype "bidirectional"))
      (node (ref "R36") (pin "P$2") (pinfunction "P$2_P$2") (pintype "passive"))
      (node (ref "R38") (pin "P$2") (pinfunction "P$2_P$2") (pintype "passive"))
    )
    (net (code "46") (name "/ODD2-") (class "Default")
      (node (ref "R37") (pin "P$1") (pinfunction "P$1_P$1") (pintype "passive"))
      (node (ref "U1") (pin "53") (pinfunction "53_53") (pintype "bidirectional"))
    )
    (net (code "47") (name "/ODD2-_RN") (class "Default")
      (node (ref "J2") (pin "P$11") (pinfunction "PIN10_P$11") (pintype "bidirectional"))
      (node (ref "R37") (pin "P$2") (pinfunction "P$2_P$2") (pintype "passive"))
      (node (ref "R38") (pin "P$1") (pinfunction "P$1_P$1") (pintype "passive"))
    )
    (net (code "48") (name "/ODDC+") (class "Default")
      (node (ref "R39") (pin "P$1") (pinfunction "P$1_P$1") (pintype "passive"))
      (node (ref "U1") (pin "54") (pinfunction "54_54") (pintype "bidirectional"))
    )
    (net (code "49") (name "/ODDC+_RN") (class "Default")
      (node (ref "J2") (pin "P$16") (pinfunction "PIN15_P$16") (pintype "bidirectional"))
      (node (ref "R39") (pin "P$2") (pinfunction "P$2_P$2") (pintype "passive"))
      (node (ref "R41") (pin "P$2") (pinfunction "P$2_P$2") (pintype "passive"))
    )
    (net (code "50") (name "/ODDC-") (class "Default")
      (node (ref "R40") (pin "P$1") (pinfunction "P$1_P$1") (pintype "passive"))
      (node (ref "U1") (pin "55") (pinfunction "55_55") (pintype "bidirectional"))
    )
    (net (code "51") (name "/ODDC-_RN") (class "Default")
      (node (ref "J2") (pin "P$15") (pinfunction "PIN14_P$15") (pintype "bidirectional"))
      (node (ref "R40") (pin "P$2") (pinfunction "P$2_P$2") (pintype "passive"))
      (node (ref "R41") (pin "P$1") (pinfunction "P$1_P$1") (pintype "passive"))
    )
    (net (code "52") (name "/PIN_1") (class "Default")
      (node (ref "R13") (pin "P$1") (pinfunction "P$1_P$1") (pintype "passive"))
      (node (ref "U1") (pin "1") (pinfunction "1_1") (pintype "bidirectional"))
    )
    (net (code "53") (name "/PIN_2") (class "Default")
      (node (ref "R14") (pin "P$1") (pinfunction "P$1_P$1") (pintype "passive"))
      (node (ref "U1") (pin "2") (pinfunction "2_2") (pintype "bidirectional"))
    )
    (net (code "54") (name "/PIN_3") (class "Default")
      (node (ref "U1") (pin "3") (pinfunction "3_3") (pintype "bidirectional"))
    )
    (net (code "55") (name "/PIN_7") (class "Default")
      (node (ref "U1") (pin "7") (pinfunction "7_7") (pintype "bidirectional"))
    )
    (net (code "56") (name "/PIN_11") (class "Default")
      (node (ref "U1") (pin "11") (pinfunction "11_11") (pintype "bidirectional"))
    )
    (net (code "57") (name "/PIN_23") (class "Default")
      (node (ref "U1") (pin "23") (pinfunction "23_23") (pintype "bidirectional"))
    )
    (net (code "58") (name "/PIN_24") (class "Default")
      (node (ref "U1") (pin "24") (pinfunction "24_24") (pintype "bidirectional"))
    )
    (net (code "59") (name "/PIN_28") (class "Default")
      (node (ref "U1") (pin "28") (pinfunction "28_28") (pintype "bidirectional"))
    )
    (net (code "60") (name "/PIN_30") (class "Default")
      (node (ref "U1") (pin "30") (pinfunction "30_30") (pintype "bidirectional"))
    )
    (net (code "61") (name "/PIN_31") (class "Default")
      (node (ref "U1") (pin "31") (pinfunction "31_31") (pintype "bidirectional"))
    )
    (net (code "62") (name "/PIN_32") (class "Default")
      (node (ref "U1") (pin "32") (pinfunction "32_32") (pintype "bidirectional"))
    )
    (net (code "63") (name "/PIN_33") (class "Default")
      (node (ref "U1") (pin "33") (pinfunction "33_33") (pintype "bidirectional"))
    )
    (net (code "64") (name "/PIN_34") (class "Default")
      (node (ref "U1") (pin "34") (pinfunction "34_34") (pintype "bidirectional"))
    )
    (net (code "65") (name "/PIN_42") (class "Default")
      (node (ref "U1") (pin "42") (pinfunction "42_42") (pintype "bidirectional"))
    )
    (net (code "66") (name "/PIN_43") (class "Default")
      (node (ref "U1") (pin "43") (pinfunction "43_43") (pintype "bidirectional"))
    )
    (net (code "67") (name "/PIN_44") (class "Default")
      (node (ref "U1") (pin "44") (pinfunction "44_44") (pintype "bidirectional"))
    )
    (net (code "68") (name "/PIN_46") (class "Default")
      (node (ref "U1") (pin "46") (pinfunction "46_46") (pintype "bidirectional"))
    )
    (net (code "69") (name "/PIN_51") (class "Default")
      (node (ref "U1") (pin "51") (pinfunction "51_51") (pintype "bidirectional"))
    )
    (net (code "70") (name "/PIN_58") (class "Default")
      (node (ref "U1") (pin "58") (pinfunction "58_58") (pintype "bidirectional"))
    )
    (net (code "71") (name "/PIN_64") (class "Default")
      (node (ref "U1") (pin "64") (pinfunction "64_64") (pintype "bidirectional"))
    )
    (net (code "72") (name "/PIN_65") (class "Default")
      (node (ref "U1") (pin "65") (pinfunction "65_65") (pintype "bidirectional"))
    )
    (net (code "73") (name "/PIN_66") (class "Default")
      (node (ref "U1") (pin "66") (pinfunction "66_66") (pintype "bidirectional"))
    )
    (net (code "74") (name "/PIN_67") (class "Default")
      (node (ref "U1") (pin "67") (pinfunction "67_67") (pintype "bidirectional"))
    )
    (net (code "75") (name "/PIN_68") (class "Default")
      (node (ref "U1") (pin "68") (pinfunction "68_68") (pintype "bidirectional"))
    )
    (net (code "76") (name "/PIN_69") (class "Default")
      (node (ref "U1") (pin "69") (pinfunction "69_69") (pintype "bidirectional"))
    )
    (net (code "77") (name "/PIN_72") (class "Default")
      (node (ref "U1") (pin "72") (pinfunction "72_72") (pintype "bidirectional"))
    )
    (net (code "78") (name "/PIN_73") (class "Default")
      (node (ref "J5") (pin "P$1") (pinfunction "PIN0_P$1") (pintype "bidirectional"))
      (node (ref "U1") (pin "73") (pinfunction "73_73") (pintype "bidirectional"))
    )
    (net (code "79") (name "/PIN_74") (class "Default")
      (node (ref "J6") (pin "P$1") (pinfunction "PIN0_P$1") (pintype "bidirectional"))
      (node (ref "U1") (pin "74") (pinfunction "74_74") (pintype "bidirectional"))
    )
    (net (code "80") (name "/PIN_75") (class "Default")
      (node (ref "J5") (pin "P$2") (pinfunction "PIN1_P$2") (pintype "bidirectional"))
      (node (ref "U1") (pin "75") (pinfunction "75_75") (pintype "bidirectional"))
    )
    (net (code "81") (name "/PIN_76") (class "Default")
      (node (ref "J6") (pin "P$2") (pinfunction "PIN1_P$2") (pintype "bidirectional"))
      (node (ref "U1") (pin "76") (pinfunction "76_76") (pintype "bidirectional"))
    )
    (net (code "82") (name "/PIN_77") (class "Default")
      (node (ref "J5") (pin "P$3") (pinfunction "PIN2_P$3") (pintype "bidirectional"))
      (node (ref "U1") (pin "77") (pinfunction "77_77") (pintype "bidirectional"))
    )
    (net (code "83") (name "/PIN_80") (class "Default")
      (node (ref "U1") (pin "80") (pinfunction "80_80") (pintype "bidirectional"))
    )
    (net (code "84") (name "/PIN_83") (class "Default")
      (node (ref "J6") (pin "P$3") (pinfunction "PIN2_P$3") (pintype "bidirectional"))
      (node (ref "U1") (pin "83") (pinfunction "83_83") (pintype "bidirectional"))
    )
    (net (code "85") (name "/PIN_86") (class "Default")
      (node (ref "J5") (pin "P$4") (pinfunction "PIN3_P$4") (pintype "bidirectional"))
      (node (ref "U1") (pin "86") (pinfunction "86_86") (pintype "bidirectional"))
    )
    (net (code "86") (name "/PIN_87") (class "Default")
      (node (ref "J6") (pin "P$4") (pinfunction "PIN3_P$4") (pintype "bidirectional"))
      (node (ref "U1") (pin "87") (pinfunction "87_87") (pintype "bidirectional"))
    )
    (net (code "87") (name "/PIN_88") (class "Default")
      (node (ref "J5") (pin "P$5") (pinfunction "PIN4_P$5") (pintype "bidirectional"))
      (node (ref "U1") (pin "88") (pinfunction "88_88") (pintype "bidirectional"))
    )
    (net (code "88") (name "/PIN_89") (class "Default")
      (node (ref "J6") (pin "P$5") (pinfunction "PIN4_P$5") (pintype "bidirectional"))
      (node (ref "U1") (pin "89") (pinfunction "89_89") (pintype "bidirectional"))
    )
    (net (code "89") (name "/PIN_90") (class "Default")
      (node (ref "U1") (pin "90") (pinfunction "90_90") (pintype "bidirectional"))
    )
    (net (code "90") (name "/PIN_91") (class "Default")
      (node (ref "U1") (pin "91") (pinfunction "91_91") (pintype "bidirectional"))
    )
    (net (code "91") (name "/PIN_98") (class "Default")
      (node (ref "J5") (pin "P$6") (pinfunction "PIN5_P$6") (pintype "bidirectional"))
      (node (ref "U1") (pin "98") (pinfunction "98_98") (pintype "bidirectional"))
    )
    (net (code "92") (name "/PIN_99") (class "Default")
      (node (ref "J6") (pin "P$6") (pinfunction "PIN5_P$6") (pintype "bidirectional"))
      (node (ref "U1") (pin "99") (pinfunction "99_99") (pintype "bidirectional"))
    )
    (net (code "93") (name "/PIN_100") (class "Default")
      (node (ref "J5") (pin "P$7") (pinfunction "PIN6_P$7") (pintype "bidirectional"))
      (node (ref "U1") (pin "100") (pinfunction "100_100") (pintype "bidirectional"))
    )
    (net (code "94") (name "/PIN_101") (class "Default")
      (node (ref "J6") (pin "P$7") (pinfunction "PIN6_P$7") (pintype "bidirectional"))
      (node (ref "U1") (pin "101") (pinfunction "101_101") (pintype "bidirectional"))
    )
    (net (code "95") (name "/PIN_103") (class "Default")
      (node (ref "J5") (pin "P$8") (pinfunction "PIN7_P$8") (pintype "bidirectional"))
      (node (ref "U1") (pin "103") (pinfunction "103_103") (pintype "bidirectional"))
    )
    (net (code "96") (name "/PIN_104") (class "Default")
      (node (ref "J6") (pin "P$8") (pinfunction "PIN7_P$8") (pintype "bidirectional"))
      (node (ref "U1") (pin "104") (pinfunction "104_104") (pintype "bidirectional"))
    )
    (net (code "97") (name "/PIN_105") (class "Default")
      (node (ref "J5") (pin "P$9") (pinfunction "PIN8_P$9") (pintype "bidirectional"))
      (node (ref "U1") (pin "105") (pinfunction "105_105") (pintype "bidirectional"))
    )
    (net (code "98") (name "/PIN_106") (class "Default")
      (node (ref "J6") (pin "P$9") (pinfunction "PIN8_P$9") (pintype "bidirectional"))
      (node (ref "U1") (pin "106") (pinfunction "106_106") (pintype "bidirectional"))
    )
    (net (code "99") (name "/PIN_110") (class "Default")
      (node (ref "R8") (pin "P$2") (pinfunction "P$2_P$2") (pintype "passive"))
      (node (ref "SW1") (pin "P$2") (pinfunction "P$2_P$2") (pintype "bidirectional"))
      (node (ref "U1") (pin "110") (pinfunction "110_110") (pintype "bidirectional"))
    )
    (net (code "100") (name "/PIN_111") (class "Default")
      (node (ref "R12") (pin "P$2") (pinfunction "P$2_P$2") (pintype "passive"))
      (node (ref "SW2") (pin "P$2") (pinfunction "P$2_P$2") (pintype "bidirectional"))
      (node (ref "U1") (pin "111") (pinfunction "111_111") (pintype "bidirectional"))
    )
    (net (code "101") (name "/PIN_112") (class "Default")
      (node (ref "R29") (pin "P$2") (pinfunction "P$2_P$2") (pintype "passive"))
      (node (ref "SW3") (pin "P$2") (pinfunction "P$2_P$2") (pintype "bidirectional"))
      (node (ref "U1") (pin "112") (pinfunction "112_112") (pintype "bidirectional"))
    )
    (net (code "102") (name "/PIN_113") (class "Default")
      (node (ref "U1") (pin "113") (pinfunction "113_113") (pintype "bidirectional"))
    )
    (net (code "103") (name "/PIN_114") (class "Default")
      (node (ref "U1") (pin "114") (pinfunction "114_114") (pintype "bidirectional"))
    )
    (net (code "104") (name "/PIN_115") (class "Default")
      (node (ref "U1") (pin "115") (pinfunction "115_115") (pintype "bidirectional"))
    )
    (net (code "105") (name "/PIN_119") (class "Default")
      (node (ref "U1") (pin "119") (pinfunction "119_119") (pintype "bidirectional"))
    )
    (net (code "106") (name "/PIN_124") (class "Default")
      (node (ref "U1") (pin "124") (pinfunction "124_124") (pintype "bidirectional"))
    )
    (net (code "107") (name "/PIN_126") (class "Default")
      (node (ref "U1") (pin "126") (pinfunction "126_126") (pintype "bidirectional"))
    )
    (net (code "108") (name "/PIN_127") (class "Default")
      (node (ref "U1") (pin "127") (pinfunction "127_127") (pintype "bidirectional"))
    )
    (net (code "109") (name "/PIN_128") (class "Default")
      (node (ref "U1") (pin "128") (pinfunction "128_128") (pintype "bidirectional"))
    )
    (net (code "110") (name "/PIN_129") (class "Default")
      (node (ref "U1") (pin "129") (pinfunction "129_129") (pintype "bidirectional"))
    )
    (net (code "111") (name "/PIN_132") (class "Default")
      (node (ref "U1") (pin "132") (pinfunction "132_132") (pintype "bidirectional"))
    )
    (net (code "112") (name "/PIN_133") (class "Default")
      (node (ref "U1") (pin "133") (pinfunction "133_133") (pintype "bidirectional"))
    )
    (net (code "113") (name "/PIN_136") (class "Default")
      (node (ref "U1") (pin "136") (pinfunction "136_136") (pintype "bidirectional"))
    )
    (net (code "114") (name "/PWM{slash}EN") (class "Default")
      (node (ref "J3") (pin "P$4") (pinfunction "4_P$4") (pintype "passive"))
      (node (ref "U1") (pin "10") (pinfunction "10_10") (pintype "bidirectional"))
    )
    (net (code "115") (name "/REG0") (class "Default")
      (node (ref "R20") (pin "P$1") (pinfunction "P$1_P$1") (pintype "passive"))
      (node (ref "R27") (pin "P$1") (pinfunction "P$1_P$1") (pintype "passive"))
      (node (ref "U6") (pin "16") (pinfunction "B6_16") (pintype "bidirectional"))
    )
    (net (code "116") (name "/REG0_LS") (class "Default")
      (node (ref "U1") (pin "137") (pinfunction "137_137") (pintype "bidirectional"))
      (node (ref "U6") (pin "8") (pinfunction "A6_8") (pintype "bidirectional"))
    )
    (net (code "117") (name "/REG1") (class "Default")
      (node (ref "R19") (pin "P$1") (pinfunction "P$1_P$1") (pintype "passive"))
      (node (ref "R26") (pin "P$1") (pinfunction "P$1_P$1") (pintype "passive"))
      (node (ref "U6") (pin "17") (pinfunction "B5_17") (pintype "bidirectional"))
    )
    (net (code "118") (name "/REG1_LS") (class "Default")
      (node (ref "U1") (pin "138") (pinfunction "138_138") (pintype "bidirectional"))
      (node (ref "U6") (pin "7") (pinfunction "A5_7") (pintype "bidirectional"))
    )
    (net (code "119") (name "/REG2") (class "Default")
      (node (ref "R18") (pin "P$1") (pinfunction "P$1_P$1") (pintype "passive"))
      (node (ref "R25") (pin "P$1") (pinfunction "P$1_P$1") (pintype "passive"))
      (node (ref "U6") (pin "18") (pinfunction "B4_18") (pintype "bidirectional"))
    )
    (net (code "120") (name "/REG2_LS") (class "Default")
      (node (ref "U1") (pin "141") (pinfunction "141_141") (pintype "bidirectional"))
      (node (ref "U6") (pin "6") (pinfunction "A4_6") (pintype "bidirectional"))
    )
    (net (code "121") (name "/RESET") (class "Default")
      (node (ref "!RESET") (pin "P$2") (pinfunction "P$2_P$2") (pintype "bidirectional"))
      (node (ref "R7") (pin "P$2") (pinfunction "P$2_P$2") (pintype "passive"))
      (node (ref "U1") (pin "125") (pinfunction "125_125") (pintype "bidirectional"))
    )
    (net (code "122") (name "/TCK") (class "Default")
      (node (ref "J1") (pin "1") (pinfunction "PIN1_1") (pintype "bidirectional"))
      (node (ref "R1") (pin "P$2") (pinfunction "P$2_P$2") (pintype "passive"))
      (node (ref "U1") (pin "16") (pinfunction "16_16") (pintype "bidirectional"))
    )
    (net (code "123") (name "/TDI") (class "Default")
      (node (ref "J1") (pin "9") (pinfunction "PIN9_9") (pintype "bidirectional"))
      (node (ref "R3") (pin "P$1") (pinfunction "P$1_P$1") (pintype "passive"))
      (node (ref "U1") (pin "15") (pinfunction "15_15") (pintype "bidirectional"))
    )
    (net (code "124") (name "/TDO") (class "Default")
      (node (ref "J1") (pin "3") (pinfunction "PIN3_3") (pintype "bidirectional"))
      (node (ref "U1") (pin "20") (pinfunction "20_20") (pintype "bidirectional"))
    )
    (net (code "125") (name "/TMS") (class "Default")
      (node (ref "J1") (pin "5") (pinfunction "PIN5_5") (pintype "bidirectional"))
      (node (ref "R2") (pin "P$1") (pinfunction "P$1_P$1") (pintype "passive"))
      (node (ref "U1") (pin "18") (pinfunction "18_18") (pintype "bidirectional"))
    )
    (net (code "126") (name "/VCCB") (class "Default")
      (node (ref "U6") (pin "23") (pinfunction "VCCB_23") (pintype "bidirectional"))
      (node (ref "U6") (pin "24") (pinfunction "VCCB_24") (pintype "bidirectional"))
      (node (ref "VOLT_SW") (pin "P$2") (pinfunction "PIN1_P$2") (pintype "bidirectional"))
    )
    (net (code "127") (name "/~{CONFIG}") (class "Default")
      (node (ref "!CONFIG") (pin "P$2") (pinfunction "P$2_P$2") (pintype "bidirectional"))
      (node (ref "R5") (pin "P$2") (pinfunction "P$2_P$2") (pintype "passive"))
      (node (ref "U1") (pin "14") (pinfunction "14_14") (pintype "bidirectional"))
    )
    (net (code "128") (name "/~{CSO}") (class "Default")
      (node (ref "R11") (pin "P$2") (pinfunction "P$2_P$2") (pintype "passive"))
      (node (ref "U1") (pin "8") (pinfunction "8_8") (pintype "bidirectional"))
      (node (ref "U5") (pin "1") (pinfunction "~{S}_1") (pintype "bidirectional"))
    )
    (net (code "129") (name "/~{STATUS}") (class "Default")
      (node (ref "R4") (pin "P$2") (pinfunction "P$2_P$2") (pintype "passive"))
      (node (ref "U1") (pin "9") (pinfunction "9_9") (pintype "bidirectional"))
    )
    (net (code "130") (name "Net-(D1-PadANODE)") (class "Default")
      (node (ref "D1") (pin "ANODE") (pinfunction "ANODE_ANODE") (pintype "power_in"))
      (node (ref "R13") (pin "P$2") (pinfunction "P$2_P$2") (pintype "passive"))
    )
    (net (code "131") (name "Net-(D2-PadANODE)") (class "Default")
      (node (ref "D2") (pin "ANODE") (pinfunction "ANODE_ANODE") (pintype "power_in"))
      (node (ref "R14") (pin "P$2") (pinfunction "P$2_P$2") (pintype "passive"))
    )
    (net (code "132") (name "Net-(J4-PIN1)") (class "Default")
      (node (ref "J4") (pin "1") (pinfunction "PIN1_1") (pintype "bidirectional"))
      (node (ref "R15") (pin "P$2") (pinfunction "P$2_P$2") (pintype "passive"))
    )
    (net (code "133") (name "Net-(J4-PIN3)") (class "Default")
      (node (ref "J4") (pin "3") (pinfunction "PIN3_3") (pintype "bidirectional"))
      (node (ref "R16") (pin "P$2") (pinfunction "P$2_P$2") (pintype "passive"))
    )
    (net (code "134") (name "Net-(J4-PIN5)") (class "Default")
      (node (ref "J4") (pin "5") (pinfunction "PIN5_5") (pintype "bidirectional"))
      (node (ref "R17") (pin "P$2") (pinfunction "P$2_P$2") (pintype "passive"))
    )
    (net (code "135") (name "Net-(J4-PIN7)") (class "Default")
      (node (ref "J4") (pin "7") (pinfunction "PIN7_7") (pintype "bidirectional"))
      (node (ref "R18") (pin "P$2") (pinfunction "P$2_P$2") (pintype "passive"))
    )
    (net (code "136") (name "Net-(J4-PIN9)") (class "Default")
      (node (ref "J4") (pin "9") (pinfunction "PIN9_9") (pintype "bidirectional"))
      (node (ref "R19") (pin "P$2") (pinfunction "P$2_P$2") (pintype "passive"))
    )
    (net (code "137") (name "Net-(J4-PIN11)") (class "Default")
      (node (ref "J4") (pin "11") (pinfunction "PIN11_11") (pintype "bidirectional"))
      (node (ref "R20") (pin "P$2") (pinfunction "P$2_P$2") (pintype "passive"))
    )
    (net (code "138") (name "Net-(J4-PIN13)") (class "Default")
      (node (ref "J4") (pin "13") (pinfunction "PIN13_13") (pintype "bidirectional"))
      (node (ref "R21") (pin "P$2") (pinfunction "P$2_P$2") (pintype "passive"))
    )
    (net (code "139") (name "unconnected-(!CONFIG-PadP$1)") (class "Default")
      (node (ref "!CONFIG") (pin "P$1") (pinfunction "P$1_P$1") (pintype "bidirectional"))
    )
    (net (code "140") (name "unconnected-(!CONFIG-PadP$3)") (class "Default")
      (node (ref "!CONFIG") (pin "P$3") (pinfunction "P$3_P$3") (pintype "bidirectional"))
    )
    (net (code "141") (name "unconnected-(!RESET-PadP$1)") (class "Default")
      (node (ref "!RESET") (pin "P$1") (pinfunction "P$1_P$1") (pintype "bidirectional"))
    )
    (net (code "142") (name "unconnected-(!RESET-PadP$3)") (class "Default")
      (node (ref "!RESET") (pin "P$3") (pinfunction "P$3_P$3") (pintype "bidirectional"))
    )
    (net (code "143") (name "unconnected-(J1-PIN6-Pad6)") (class "Default")
      (node (ref "J1") (pin "6") (pinfunction "PIN6_6") (pintype "bidirectional"))
    )
    (net (code "144") (name "unconnected-(J1-PIN7-Pad7)") (class "Default")
      (node (ref "J1") (pin "7") (pinfunction "PIN7_7") (pintype "bidirectional"))
    )
    (net (code "145") (name "unconnected-(J1-PIN8-Pad8)") (class "Default")
      (node (ref "J1") (pin "8") (pinfunction "PIN8_8") (pintype "bidirectional"))
    )
    (net (code "146") (name "unconnected-(J2-PIN3-PadP$4)") (class "Default")
      (node (ref "J2") (pin "P$4") (pinfunction "PIN3_P$4") (pintype "bidirectional"))
    )
    (net (code "147") (name "unconnected-(J2-PIN16-PadP$17)") (class "Default")
      (node (ref "J2") (pin "P$17") (pinfunction "PIN16_P$17") (pintype "bidirectional"))
    )
    (net (code "148") (name "unconnected-(J2-PIN17-PadP$18)") (class "Default")
      (node (ref "J2") (pin "P$18") (pinfunction "PIN17_P$18") (pintype "bidirectional"))
    )
    (net (code "149") (name "unconnected-(J2-PIN28-PadP$29)") (class "Default")
      (node (ref "J2") (pin "P$29") (pinfunction "PIN28_P$29") (pintype "bidirectional"))
    )
    (net (code "150") (name "unconnected-(J2-PIN29-PadP$30)") (class "Default")
      (node (ref "J2") (pin "P$30") (pinfunction "PIN29_P$30") (pintype "bidirectional"))
    )
    (net (code "151") (name "unconnected-(J3-3-PadP$3)") (class "Default")
      (node (ref "J3") (pin "P$3") (pinfunction "3_P$3") (pintype "passive"))
    )
    (net (code "152") (name "unconnected-(SW1-PadP$1)") (class "Default")
      (node (ref "SW1") (pin "P$1") (pinfunction "P$1_P$1") (pintype "bidirectional"))
    )
    (net (code "153") (name "unconnected-(SW1-PadP$3)") (class "Default")
      (node (ref "SW1") (pin "P$3") (pinfunction "P$3_P$3") (pintype "bidirectional"))
    )
    (net (code "154") (name "unconnected-(SW2-PadP$1)") (class "Default")
      (node (ref "SW2") (pin "P$1") (pinfunction "P$1_P$1") (pintype "bidirectional"))
    )
    (net (code "155") (name "unconnected-(SW2-PadP$3)") (class "Default")
      (node (ref "SW2") (pin "P$3") (pinfunction "P$3_P$3") (pintype "bidirectional"))
    )
    (net (code "156") (name "unconnected-(SW3-PadP$1)") (class "Default")
      (node (ref "SW3") (pin "P$1") (pinfunction "P$1_P$1") (pintype "bidirectional"))
    )
    (net (code "157") (name "unconnected-(SW3-PadP$3)") (class "Default")
      (node (ref "SW3") (pin "P$3") (pinfunction "P$3_P$3") (pintype "bidirectional"))
    )
    (net (code "158") (name "unconnected-(U6-A8-Pad10)") (class "Default")
      (node (ref "U6") (pin "10") (pinfunction "A8_10") (pintype "bidirectional"))
    )
    (net (code "159") (name "unconnected-(U6-B8-Pad14)") (class "Default")
      (node (ref "U6") (pin "14") (pinfunction "B8_14") (pintype "bidirectional"))
    )
    (net (code "160") (name "unconnected-(X1-STBY-PadP$1)") (class "Default")
      (node (ref "X1") (pin "P$1") (pinfunction "STBY_P$1") (pintype "bidirectional"))
    )
  )
)
